# MPU-9250.net
KiCad netlist of a schematic drawn in EAGLE
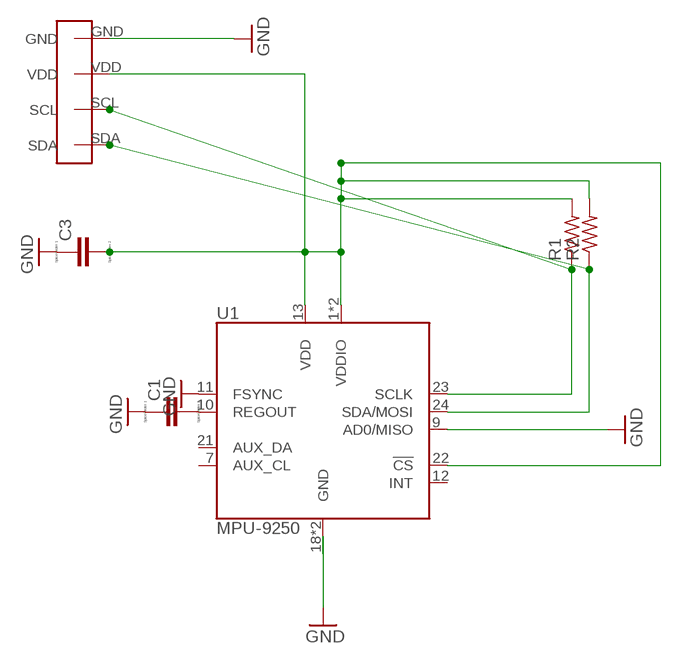
[diagram p0: schematic, sheet 1]

(export (version "E")
  (design (tool "Eeschema 10.0.6"))
  (components
    (comp (ref "C1")
      (value "CC0603")
      (footprint "eagle-import:C0603")
      (libsource (lib "eagle-import") (part "CC0603"))
    )
    (comp (ref "C3")
      (value "CC0603")
      (footprint "eagle-import:C0603")
      (libsource (lib "eagle-import") (part "CC0603"))
    )
    (comp (ref "R1")
      (value "R-US_R0603")
      (footprint "eagle-import:R0603")
      (libsource (lib "eagle-import") (part "R-US_R0603"))
    )
    (comp (ref "R2")
      (value "R-US_R0603")
      (footprint "eagle-import:R0603")
      (libsource (lib "eagle-import") (part "R-US_R0603"))
    )
    (comp (ref "U$1")
      (value "PINHEADER1MM")
      (footprint "eagle-import:PINHEADER1MM")
      (libsource (lib "eagle-import") (part "PINHEADER1MM"))
    )
    (comp (ref "U1")
      (value "MPU-9250")
      (footprint "eagle-import:QFN-24_3MM")
      (libsource (lib "eagle-import") (part "MPU-9250"))
    )
  )
  (nets
    (net (code "1") (name "GND") (class "Default")
      (node (ref "C1") (pin "1") (pinfunction "1_1") (pintype "passive"))
      (node (ref "C3") (pin "1") (pinfunction "1_1") (pintype "passive"))
      (node (ref "U$1") (pin "GND") (pinfunction "GND_GND") (pintype "bidirectional"))
      (node (ref "U1") (pin "11") (pinfunction "FSYNC_11") (pintype "bidirectional"))
      (node (ref "U1") (pin "18") (pinfunction "GND_18") (pintype "bidirectional"))
      (node (ref "U1") (pin "20") (pinfunction "GND_20") (pintype "bidirectional"))
      (node (ref "U1") (pin "9") (pinfunction "AD0/MISO_9") (pintype "bidirectional"))
    )
    (net (code "2") (name "Net-(U1-REGOUT)") (class "Default")
      (node (ref "C1") (pin "2") (pinfunction "2_2") (pintype "passive"))
      (node (ref "U1") (pin "10") (pinfunction "REGOUT_10") (pintype "bidirectional"))
    )
    (net (code "3") (name "Net-(U1-SCLK)") (class "Default")
      (node (ref "R1") (pin "1") (pinfunction "1_1") (pintype "passive"))
      (node (ref "U$1") (pin "SCL") (pinfunction "SCL_SCL") (pintype "bidirectional"))
      (node (ref "U1") (pin "23") (pinfunction "SCLK_23") (pintype "bidirectional"))
    )
    (net (code "4") (name "Net-(U1-SDA{slash}MOSI)") (class "Default")
      (node (ref "R2") (pin "1") (pinfunction "1_1") (pintype "passive"))
      (node (ref "U$1") (pin "SDA") (pinfunction "SDA_SDA") (pintype "bidirectional"))
      (node (ref "U1") (pin "24") (pinfunction "SDA/MOSI_24") (pintype "bidirectional"))
    )
    (net (code "5") (name "Net-(U1-VDD)") (class "Default")
      (node (ref "C3") (pin "2") (pinfunction "2_2") (pintype "passive"))
      (node (ref "R1") (pin "2") (pinfunction "2_2") (pintype "passive"))
      (node (ref "R2") (pin "2") (pinfunction "2_2") (pintype "passive"))
      (node (ref "U$1") (pin "VDD") (pinfunction "VDD_VDD") (pintype "bidirectional"))
      (node (ref "U1") (pin "1") (pinfunction "VDDIO_1") (pintype "bidirectional"))
      (node (ref "U1") (pin "13") (pinfunction "VDD_13") (pintype "bidirectional"))
      (node (ref "U1") (pin "22") (pinfunction "~{CS}_22") (pintype "bidirectional"))
      (node (ref "U1") (pin "8") (pinfunction "VDDIO_8") (pintype "bidirectional"))
    )
    (net (code "6") (name "unconnected-(U1-AUX_CL-Pad7)") (class "Default")
      (node (ref "U1") (pin "7") (pinfunction "AUX_CL_7") (pintype "bidirectional"))
    )
    (net (code "7") (name "unconnected-(U1-AUX_DA-Pad21)") (class "Default")
      (node (ref "U1") (pin "21") (pinfunction "AUX_DA_21") (pintype "bidirectional"))
    )
    (net (code "8") (name "unconnected-(U1-INT-Pad12)") (class "Default")
      (node (ref "U1") (pin "12") (pinfunction "INT_12") (pintype "bidirectional"))
    )
  )
)
